# KMO_IO_MV5.net
KiCad netlist of a schematic drawn in EAGLE
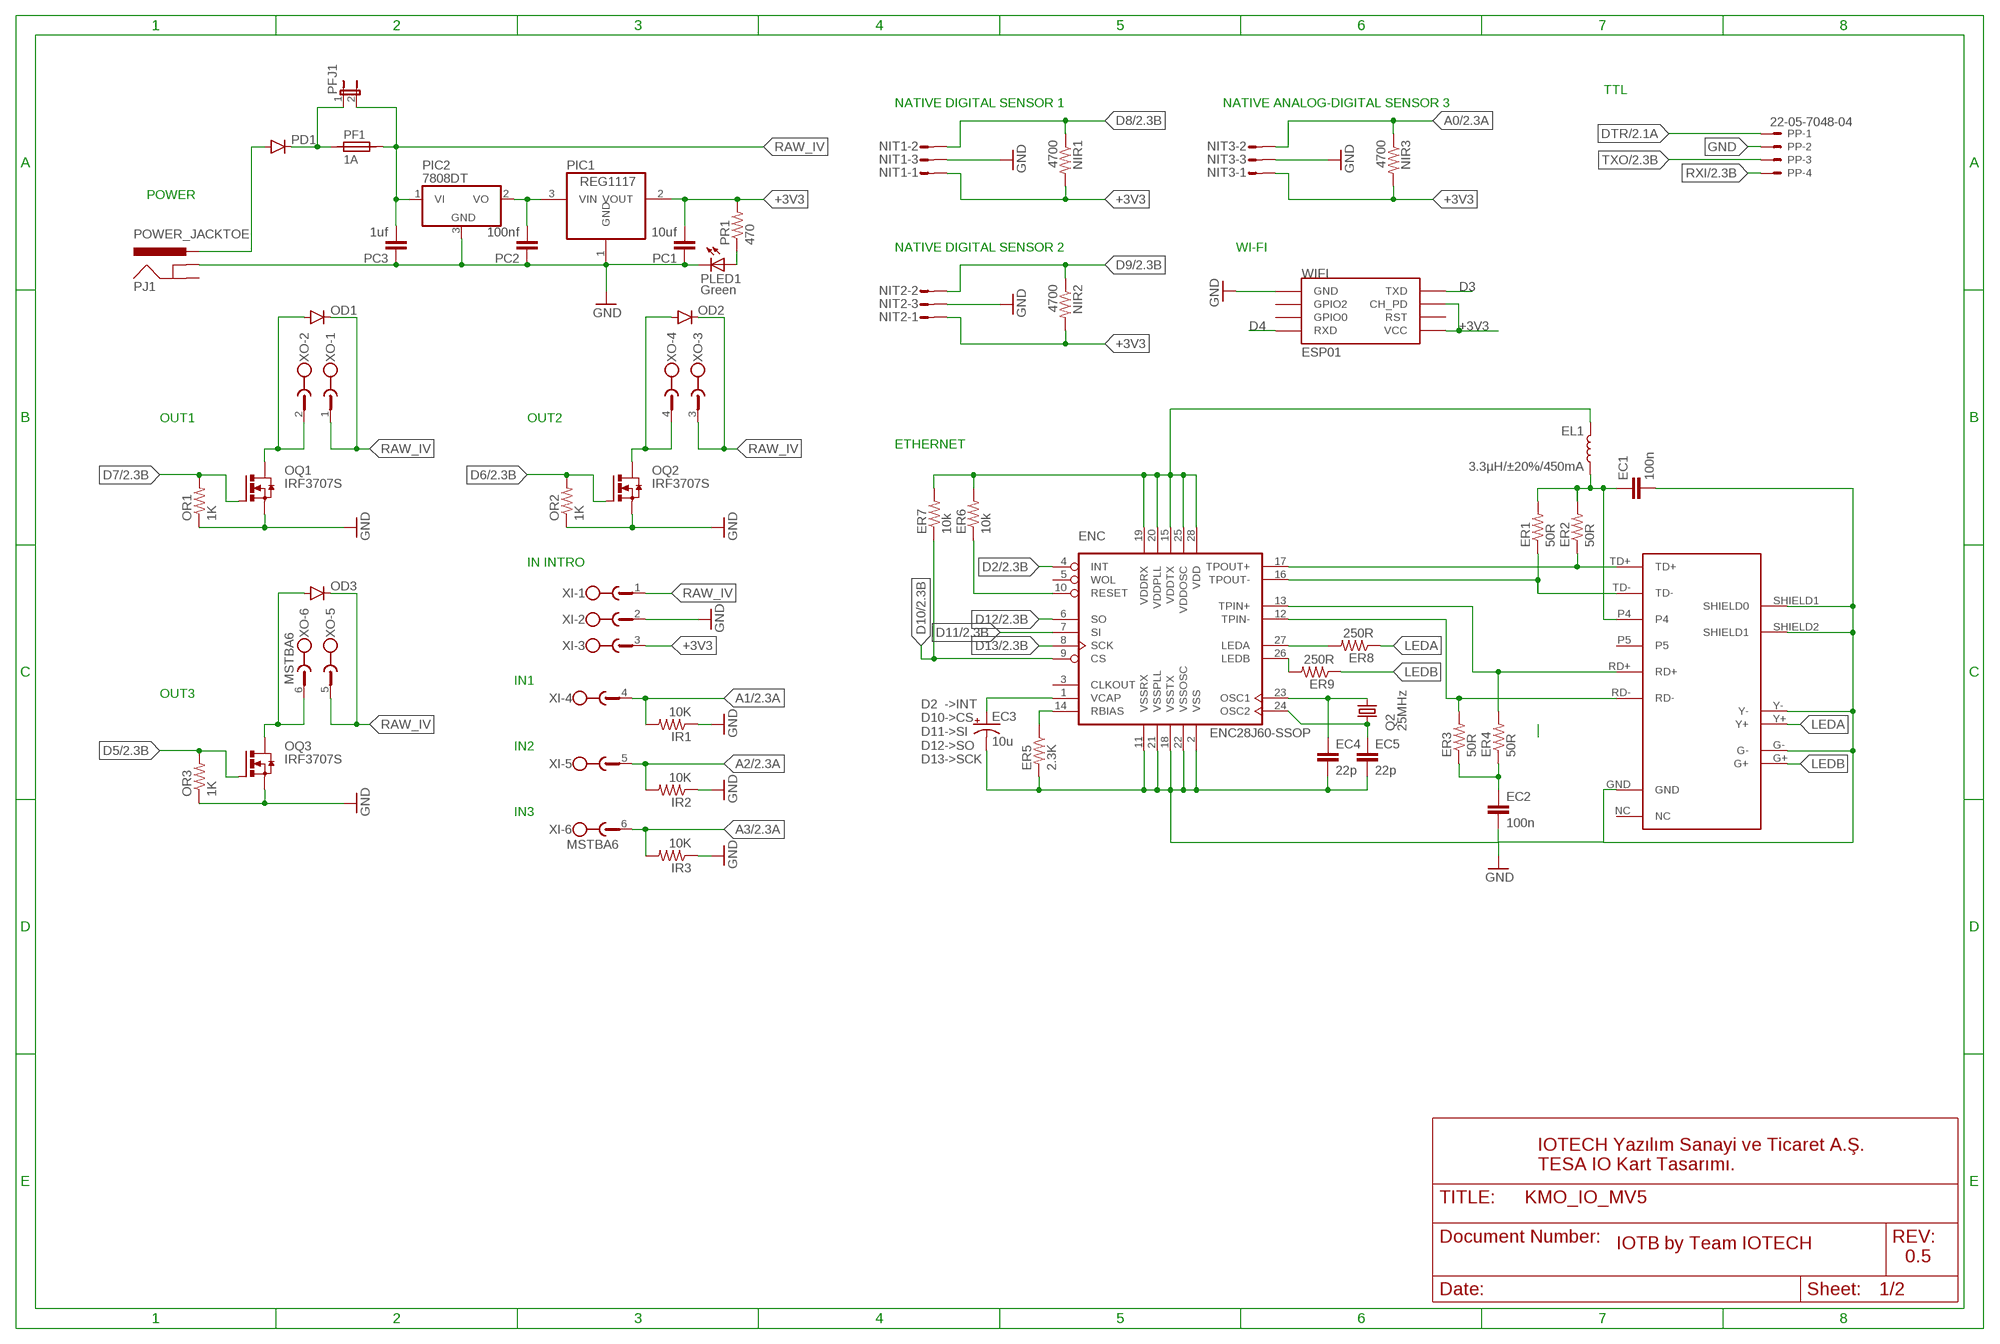
[diagram p0: schematic, sheet 1]
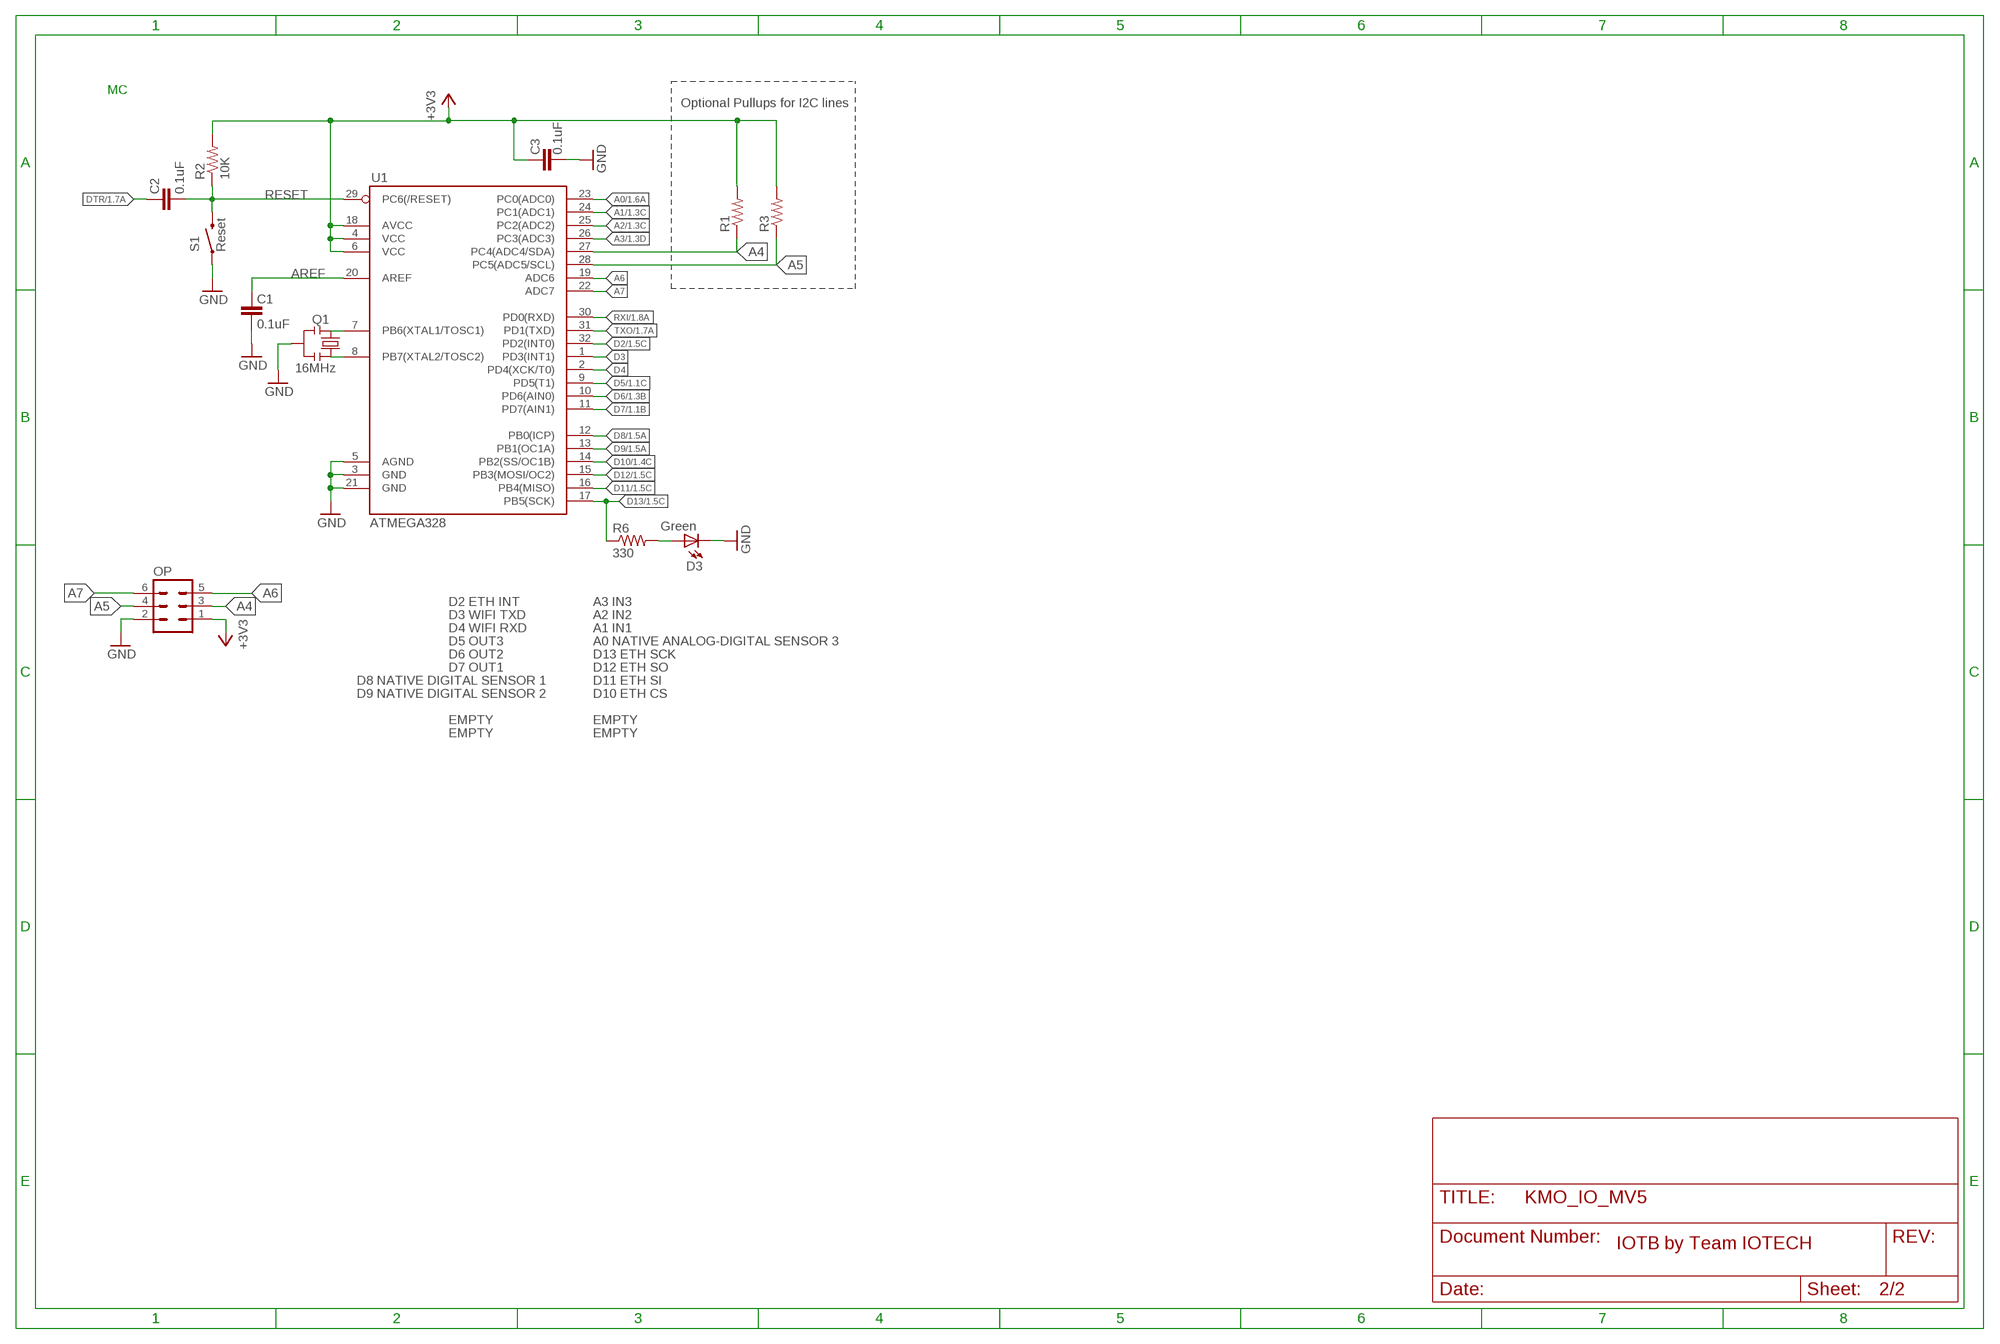
[diagram p1: schematic, sheet 2]

(export (version "E")
  (design (tool "Eeschema 10.0.6"))
  (components
    (comp (ref "C1")
      (value "0.1uF")
      (footprint "eagle-import:0805")
      (libsource (lib "eagle-import") (part "SparkFun-Passives_CAP0805"))
    )
    (comp (ref "C2")
      (value "0.1uF")
      (footprint "eagle-import:0805")
      (libsource (lib "eagle-import") (part "SparkFun-Passives_CAP0805"))
    )
    (comp (ref "C3")
      (value "0.1uF")
      (footprint "eagle-import:0805")
      (libsource (lib "eagle-import") (part "SparkFun-Passives_CAP0805"))
    )
    (comp (ref "D3")
      (value "Green")
      (footprint "eagle-import:CHIP-LED0805")
      (libsource (lib "eagle-import") (part "LEDCHIP-LED0805"))
    )
    (comp (ref "OP")
      (value "MA03-2")
      (footprint "eagle-import:MA03-2")
      (libsource (lib "eagle-import") (part "MA03-2"))
    )
    (comp (ref "Q1")
      (value "16MHz")
      (footprint "eagle-import:RESONATOR-SMD-1_1")
      (libsource (lib "eagle-import") (part "RESONATOR1{colon}1"))
    )
    (comp (ref "R1")
      (value "RESISTOR0805-RES")
      (footprint "eagle-import:0805")
      (libsource (lib "eagle-import") (part "RESISTOR0805-RES"))
    )
    (comp (ref "R2")
      (value "10K")
      (footprint "eagle-import:0805")
      (libsource (lib "eagle-import") (part "RESISTOR0805-RES"))
    )
    (comp (ref "R3")
      (value "RESISTOR0805-RES")
      (footprint "eagle-import:0805")
      (libsource (lib "eagle-import") (part "RESISTOR0805-RES"))
    )
    (comp (ref "R6")
      (value "330")
      (footprint "eagle-import:0805")
      (libsource (lib "eagle-import") (part "RESISTOR0805-RES"))
    )
    (comp (ref "S1")
      (value "Reset")
      (footprint "eagle-import:TACTILE-SWITCH-SMD-ALT01")
      (libsource (lib "eagle-import") (part "SWITCH-MOMENTARY-2SMD-ALT01"))
    )
    (comp (ref "U1")
      (value "ATMEGA328")
      (footprint "eagle-import:TQFP32-08")
      (libsource (lib "eagle-import") (part "ATMEGA168"))
    )
    (comp (ref "EC1")
      (value "100n")
      (footprint "eagle-import:0805")
      (libsource (lib "eagle-import") (part "SparkFun-Passives_CAP0805"))
    )
    (comp (ref "EC2")
      (value "100n")
      (footprint "eagle-import:0805")
      (libsource (lib "eagle-import") (part "SparkFun-Passives_CAP0805"))
    )
    (comp (ref "EC3")
      (value "10u")
      (footprint "eagle-import:EIA3216-KIT")
      (libsource (lib "eagle-import") (part "CAP_POL1206-KIT"))
    )
    (comp (ref "EC4")
      (value "22p")
      (footprint "eagle-import:0805")
      (libsource (lib "eagle-import") (part "SparkFun-Passives_CAP0805"))
    )
    (comp (ref "EC5")
      (value "22p")
      (footprint "eagle-import:0805")
      (libsource (lib "eagle-import") (part "SparkFun-Passives_CAP0805"))
    )
    (comp (ref "EL1")
      (value "3.3µH/±20%/450mA")
      (footprint "eagle-import:0805")
      (libsource (lib "eagle-import") (part "INDUCTOR-0805-3.3UH"))
    )
    (comp (ref "ENC")
      (value "ENC28J60-SSOP")
      (footprint "eagle-import:SSOP28")
      (libsource (lib "eagle-import") (part "ENC28J60-SSOP"))
    )
    (comp (ref "ER1")
      (value "50R")
      (footprint "eagle-import:0805")
      (libsource (lib "eagle-import") (part "RESISTOR0805-RES"))
    )
    (comp (ref "ER2")
      (value "50R")
      (footprint "eagle-import:0805")
      (libsource (lib "eagle-import") (part "RESISTOR0805-RES"))
    )
    (comp (ref "ER3")
      (value "50R")
      (footprint "eagle-import:0805")
      (libsource (lib "eagle-import") (part "RESISTOR0805-RES"))
    )
    (comp (ref "ER4")
      (value "50R")
      (footprint "eagle-import:0805")
      (libsource (lib "eagle-import") (part "RESISTOR0805-RES"))
    )
    (comp (ref "ER5")
      (value "2.3K")
      (footprint "eagle-import:0805")
      (libsource (lib "eagle-import") (part "RESISTOR0805-RES"))
    )
    (comp (ref "ER6")
      (value "10k")
      (footprint "eagle-import:0805")
      (libsource (lib "eagle-import") (part "RESISTOR0805-RES"))
    )
    (comp (ref "ER7")
      (value "10k")
      (footprint "eagle-import:0805")
      (libsource (lib "eagle-import") (part "RESISTOR0805-RES"))
    )
    (comp (ref "ER8")
      (value "250R")
      (footprint "eagle-import:0805")
      (libsource (lib "eagle-import") (part "RESISTOR0805-RES"))
    )
    (comp (ref "ER9")
      (value "250R")
      (footprint "eagle-import:0805")
      (libsource (lib "eagle-import") (part "RESISTOR0805-RES"))
    )
    (comp (ref "IR1")
      (value "10K")
      (footprint "eagle-import:0805")
      (libsource (lib "eagle-import") (part "RESISTOR0805-RES"))
    )
    (comp (ref "IR2")
      (value "10K")
      (footprint "eagle-import:0805")
      (libsource (lib "eagle-import") (part "RESISTOR0805-RES"))
    )
    (comp (ref "IR3")
      (value "10K")
      (footprint "eagle-import:0805")
      (libsource (lib "eagle-import") (part "RESISTOR0805-RES"))
    )
    (comp (ref "NIR1")
      (value "4700")
      (footprint "eagle-import:0805")
      (libsource (lib "eagle-import") (part "RESISTOR0805-RES"))
    )
    (comp (ref "NIR2")
      (value "4700")
      (footprint "eagle-import:0805")
      (libsource (lib "eagle-import") (part "RESISTOR0805-RES"))
    )
    (comp (ref "NIR3")
      (value "4700")
      (footprint "eagle-import:0805")
      (libsource (lib "eagle-import") (part "RESISTOR0805-RES"))
    )
    (comp (ref "NIT1")
      (value "S03P")
      (footprint "eagle-import:S03P")
      (libsource (lib "eagle-import") (part "S03P"))
    )
    (comp (ref "NIT2")
      (value "S03P")
      (footprint "eagle-import:S03P")
      (libsource (lib "eagle-import") (part "S03P"))
    )
    (comp (ref "NIT3")
      (value "S03P")
      (footprint "eagle-import:S03P")
      (libsource (lib "eagle-import") (part "S03P"))
    )
    (comp (ref "OD1")
      (value "DIODESMA")
      (footprint "eagle-import:SMA-DIODE")
      (libsource (lib "eagle-import") (part "DIODESMA"))
    )
    (comp (ref "OD2")
      (value "DIODESMA")
      (footprint "eagle-import:SMA-DIODE")
      (libsource (lib "eagle-import") (part "DIODESMA"))
    )
    (comp (ref "OD3")
      (value "DIODESMA")
      (footprint "eagle-import:SMA-DIODE")
      (libsource (lib "eagle-import") (part "DIODESMA"))
    )
    (comp (ref "OQ1")
      (value "IRF3707S")
      (footprint "eagle-import:D2PACK")
      (libsource (lib "eagle-import") (part "IRF3704S"))
    )
    (comp (ref "OQ2")
      (value "IRF3707S")
      (footprint "eagle-import:D2PACK")
      (libsource (lib "eagle-import") (part "IRF3704S"))
    )
    (comp (ref "OQ3")
      (value "IRF3707S")
      (footprint "eagle-import:D2PACK")
      (libsource (lib "eagle-import") (part "IRF3704S"))
    )
    (comp (ref "OR1")
      (value "1K")
      (footprint "eagle-import:0805")
      (libsource (lib "eagle-import") (part "RESISTOR0805-RES"))
    )
    (comp (ref "OR2")
      (value "1K")
      (footprint "eagle-import:0805")
      (libsource (lib "eagle-import") (part "RESISTOR0805-RES"))
    )
    (comp (ref "OR3")
      (value "1K")
      (footprint "eagle-import:0805")
      (libsource (lib "eagle-import") (part "RESISTOR0805-RES"))
    )
    (comp (ref "PC1")
      (value "10uf")
      (footprint "eagle-import:0805")
      (libsource (lib "eagle-import") (part "CAP0805"))
    )
    (comp (ref "PC2")
      (value "100nf")
      (footprint "eagle-import:0805")
      (libsource (lib "eagle-import") (part "CAP0805"))
    )
    (comp (ref "PC3")
      (value "1uf")
      (footprint "eagle-import:0805")
      (libsource (lib "eagle-import") (part "CAP0805"))
    )
    (comp (ref "PD1")
      (value "DIODESMA")
      (footprint "eagle-import:SMA-DIODE")
      (libsource (lib "eagle-import") (part "DIODESMA"))
    )
    (comp (ref "PF1")
      (value "1A")
      (footprint "eagle-import:1820")
      (libsource (lib "eagle-import") (part "SIBA194600"))
    )
    (comp (ref "PFJ1")
      (value "JP1E")
      (footprint "eagle-import:JP1")
      (libsource (lib "eagle-import") (part "JP1E"))
    )
    (comp (ref "PIC1")
      (value "REG1117")
      (footprint "eagle-import:SOT223")
      (libsource (lib "eagle-import") (part "REG1117"))
    )
    (comp (ref "PIC2")
      (value "7808DT")
      (footprint "eagle-import:TO252")
      (libsource (lib "eagle-import") (part "78DT08"))
    )
    (comp (ref "PJ1")
      (value "POWER_JACKTOE")
      (footprint "eagle-import:POWER_JACK_SMD_OVERPASTE_TOE")
      (libsource (lib "eagle-import") (part "POWER_JACKTOE"))
    )
    (comp (ref "PLED1")
      (value "Green")
      (footprint "eagle-import:CHIP-LED0805")
      (libsource (lib "eagle-import") (part "LEDCHIP-LED0805"))
    )
    (comp (ref "PP")
      (value "22-05-7048-04")
      (footprint "eagle-import:7395-04")
      (fields (field (name "MF") "MOLEX"))
      (libsource (lib "eagle-import") (part "22-?-0405-7048"))
    )
    (comp (ref "PR1")
      (value "470")
      (footprint "eagle-import:0805")
      (libsource (lib "eagle-import") (part "RESISTOR0805-RES"))
    )
    (comp (ref "Q2")
      (value "25MHz")
      (footprint "eagle-import:5.0X3.2_2")
      (libsource (lib "eagle-import") (part "KX-9B"))
    )
    (comp (ref "U$2")
      (value "HR911105A")
      (footprint "eagle-import:RJ45")
      (libsource (lib "eagle-import") (part "HR911105A"))
    )
    (comp (ref "WIFI")
      (value "ESP01")
      (footprint "eagle-import:ESP01")
      (libsource (lib "eagle-import") (part "ESP01"))
    )
    (comp (ref "XI")
      (value "MSTBA6")
      (footprint "eagle-import:MSTBA6")
      (fields (field (name "MF") "FARNELL") (field (name "MPN") "1757284"))
      (libsource (lib "eagle-import") (part "MSTBA6"))
    )
    (comp (ref "XO")
      (value "MSTBA6")
      (footprint "eagle-import:MSTBA6")
      (fields (field (name "MF") "FARNELL") (field (name "MPN") "1757284"))
      (libsource (lib "eagle-import") (part "MSTBA6"))
    )
  )
  (nets
    (net (code "1") (name "+3V3") (class "Default")
      (node (ref "C3") (pin "2") (pinfunction "2_2") (pintype "passive"))
      (node (ref "EL1") (pin "1") (pinfunction "1_1") (pintype "passive"))
      (node (ref "ENC") (pin "15") (pinfunction "VDDTX_15") (pintype "power_in"))
      (node (ref "ENC") (pin "19") (pinfunction "VDDRX_19") (pintype "power_in"))
      (node (ref "ENC") (pin "20") (pinfunction "VDDPLL_20") (pintype "power_in"))
      (node (ref "ENC") (pin "25") (pinfunction "VDDOSC_25") (pintype "power_in"))
      (node (ref "ENC") (pin "28") (pinfunction "VDD_28") (pintype "power_in"))
      (node (ref "ER6") (pin "2") (pinfunction "2_2") (pintype "passive"))
      (node (ref "ER7") (pin "2") (pinfunction "2_2") (pintype "passive"))
      (node (ref "NIR1") (pin "2") (pinfunction "2_2") (pintype "passive"))
      (node (ref "NIR2") (pin "2") (pinfunction "2_2") (pintype "passive"))
      (node (ref "NIR3") (pin "2") (pinfunction "2_2") (pintype "passive"))
      (node (ref "NIT1") (pin "1") (pinfunction "S_1") (pintype "passive"))
      (node (ref "NIT2") (pin "1") (pinfunction "S_1") (pintype "passive"))
      (node (ref "NIT3") (pin "1") (pinfunction "S_1") (pintype "passive"))
      (node (ref "OP") (pin "1") (pinfunction "1_1") (pintype "passive"))
      (node (ref "PC1") (pin "2") (pinfunction "2_2") (pintype "passive"))
      (node (ref "PIC1") (pin "2") (pinfunction "VOUT_2") (pintype "output"))
      (node (ref "PR1") (pin "2") (pinfunction "2_2") (pintype "passive"))
      (node (ref "R1") (pin "2") (pinfunction "2_2") (pintype "passive"))
      (node (ref "R2") (pin "2") (pinfunction "2_2") (pintype "passive"))
      (node (ref "R3") (pin "2") (pinfunction "2_2") (pintype "passive"))
      (node (ref "U1") (pin "18") (pinfunction "AVCC_18") (pintype "bidirectional"))
      (node (ref "U1") (pin "4") (pinfunction "VCC_4") (pintype "bidirectional"))
      (node (ref "U1") (pin "6") (pinfunction "VCC_6") (pintype "bidirectional"))
      (node (ref "WIFI") (pin "CH_PD") (pinfunction "CH_PD_CH_PD") (pintype "bidirectional"))
      (node (ref "WIFI") (pin "VCC") (pinfunction "VCC_VCC") (pintype "bidirectional"))
      (node (ref "XI") (pin "3") (pinfunction "1_3") (pintype "passive"))
    )
    (net (code "2") (name "A0") (class "Default")
      (node (ref "NIR3") (pin "1") (pinfunction "1_1") (pintype "passive"))
      (node (ref "NIT3") (pin "2") (pinfunction "S_2") (pintype "passive"))
      (node (ref "U1") (pin "23") (pinfunction "PC0(ADC0)_23") (pintype "bidirectional"))
    )
    (net (code "3") (name "A1") (class "Default")
      (node (ref "IR1") (pin "2") (pinfunction "2_2") (pintype "passive"))
      (node (ref "U1") (pin "24") (pinfunction "PC1(ADC1)_24") (pintype "bidirectional"))
      (node (ref "XI") (pin "4") (pinfunction "1_4") (pintype "passive"))
    )
    (net (code "4") (name "A2") (class "Default")
      (node (ref "IR2") (pin "2") (pinfunction "2_2") (pintype "passive"))
      (node (ref "U1") (pin "25") (pinfunction "PC2(ADC2)_25") (pintype "bidirectional"))
      (node (ref "XI") (pin "5") (pinfunction "1_5") (pintype "passive"))
    )
    (net (code "5") (name "A3") (class "Default")
      (node (ref "IR3") (pin "2") (pinfunction "2_2") (pintype "passive"))
      (node (ref "U1") (pin "26") (pinfunction "PC3(ADC3)_26") (pintype "bidirectional"))
      (node (ref "XI") (pin "6") (pinfunction "1_6") (pintype "passive"))
    )
    (net (code "6") (name "A4") (class "Default")
      (node (ref "OP") (pin "3") (pinfunction "3_3") (pintype "passive"))
      (node (ref "R1") (pin "1") (pinfunction "1_1") (pintype "passive"))
      (node (ref "U1") (pin "27") (pinfunction "PC4(ADC4/SDA)_27") (pintype "bidirectional"))
    )
    (net (code "7") (name "A5") (class "Default")
      (node (ref "OP") (pin "4") (pinfunction "4_4") (pintype "passive"))
      (node (ref "R3") (pin "1") (pinfunction "1_1") (pintype "passive"))
      (node (ref "U1") (pin "28") (pinfunction "PC5(ADC5/SCL)_28") (pintype "bidirectional"))
    )
    (net (code "8") (name "A6") (class "Default")
      (node (ref "OP") (pin "5") (pinfunction "5_5") (pintype "passive"))
      (node (ref "U1") (pin "19") (pinfunction "ADC6_19") (pintype "bidirectional"))
    )
    (net (code "9") (name "A7") (class "Default")
      (node (ref "OP") (pin "6") (pinfunction "6_6") (pintype "passive"))
      (node (ref "U1") (pin "22") (pinfunction "ADC7_22") (pintype "bidirectional"))
    )
    (net (code "10") (name "AREF") (class "Default")
      (node (ref "C1") (pin "2") (pinfunction "2_2") (pintype "passive"))
      (node (ref "U1") (pin "20") (pinfunction "AREF_20") (pintype "bidirectional"))
    )
    (net (code "11") (name "D2") (class "Default")
      (node (ref "ENC") (pin "4") (pinfunction "INT_4") (pintype "output"))
      (node (ref "U1") (pin "32") (pinfunction "PD2(INT0)_32") (pintype "bidirectional"))
    )
    (net (code "12") (name "D3") (class "Default")
      (node (ref "U1") (pin "1") (pinfunction "PD3(INT1)_1") (pintype "bidirectional"))
      (node (ref "WIFI") (pin "TX") (pinfunction "TXD_TX") (pintype "bidirectional"))
    )
    (net (code "13") (name "D4") (class "Default")
      (node (ref "U1") (pin "2") (pinfunction "PD4(XCK/T0)_2") (pintype "bidirectional"))
      (node (ref "WIFI") (pin "RX") (pinfunction "RXD_RX") (pintype "bidirectional"))
    )
    (net (code "14") (name "D5") (class "Default")
      (node (ref "OQ3") (pin "1") (pinfunction "G_1") (pintype "passive"))
      (node (ref "OR3") (pin "2") (pinfunction "2_2") (pintype "passive"))
      (node (ref "U1") (pin "9") (pinfunction "PD5(T1)_9") (pintype "bidirectional"))
    )
    (net (code "15") (name "D6") (class "Default")
      (node (ref "OQ2") (pin "1") (pinfunction "G_1") (pintype "passive"))
      (node (ref "OR2") (pin "2") (pinfunction "2_2") (pintype "passive"))
      (node (ref "U1") (pin "10") (pinfunction "PD6(AIN0)_10") (pintype "bidirectional"))
    )
    (net (code "16") (name "D7") (class "Default")
      (node (ref "OQ1") (pin "1") (pinfunction "G_1") (pintype "passive"))
      (node (ref "OR1") (pin "2") (pinfunction "2_2") (pintype "passive"))
      (node (ref "U1") (pin "11") (pinfunction "PD7(AIN1)_11") (pintype "bidirectional"))
    )
    (net (code "17") (name "D8") (class "Default")
      (node (ref "NIR1") (pin "1") (pinfunction "1_1") (pintype "passive"))
      (node (ref "NIT1") (pin "2") (pinfunction "S_2") (pintype "passive"))
      (node (ref "U1") (pin "12") (pinfunction "PB0(ICP)_12") (pintype "bidirectional"))
    )
    (net (code "18") (name "D9") (class "Default")
      (node (ref "NIR2") (pin "1") (pinfunction "1_1") (pintype "passive"))
      (node (ref "NIT2") (pin "2") (pinfunction "S_2") (pintype "passive"))
      (node (ref "U1") (pin "13") (pinfunction "PB1(OC1A)_13") (pintype "bidirectional"))
    )
    (net (code "19") (name "D10") (class "Default")
      (node (ref "ENC") (pin "9") (pinfunction "CS_9") (pintype "input"))
      (node (ref "ER7") (pin "1") (pinfunction "1_1") (pintype "passive"))
      (node (ref "U1") (pin "14") (pinfunction "PB2(SS/OC1B)_14") (pintype "bidirectional"))
    )
    (net (code "20") (name "D11") (class "Default")
      (node (ref "ENC") (pin "7") (pinfunction "SI_7") (pintype "input"))
      (node (ref "U1") (pin "16") (pinfunction "PB4(MISO)_16") (pintype "bidirectional"))
    )
    (net (code "21") (name "D12") (class "Default")
      (node (ref "ENC") (pin "6") (pinfunction "SO_6") (pintype "output"))
      (node (ref "U1") (pin "15") (pinfunction "PB3(MOSI/OC2)_15") (pintype "bidirectional"))
    )
    (net (code "22") (name "D13") (class "Default")
      (node (ref "ENC") (pin "8") (pinfunction "SCK_8") (pintype "input"))
      (node (ref "R6") (pin "1") (pinfunction "1_1") (pintype "passive"))
      (node (ref "U1") (pin "17") (pinfunction "PB5(SCK)_17") (pintype "bidirectional"))
    )
    (net (code "23") (name "DTR") (class "Default")
      (node (ref "C2") (pin "2") (pinfunction "2_2") (pintype "passive"))
      (node (ref "PP") (pin "1") (pinfunction "S_1") (pintype "passive"))
    )
    (net (code "24") (name "GND") (class "Default")
      (node (ref "C1") (pin "1") (pinfunction "1_1") (pintype "passive"))
      (node (ref "C3") (pin "1") (pinfunction "1_1") (pintype "passive"))
      (node (ref "D3") (pin "C") (pinfunction "C_C") (pintype "passive"))
      (node (ref "EC1") (pin "2") (pinfunction "2_2") (pintype "passive"))
      (node (ref "EC2") (pin "2") (pinfunction "2_2") (pintype "passive"))
      (node (ref "EC3") (pin "C") (pinfunction "-_C") (pintype "passive"))
      (node (ref "EC4") (pin "2") (pinfunction "2_2") (pintype "passive"))
      (node (ref "EC5") (pin "2") (pinfunction "2_2") (pintype "passive"))
      (node (ref "ENC") (pin "11") (pinfunction "VSSRX_11") (pintype "power_in"))
      (node (ref "ENC") (pin "18") (pinfunction "VSSTX_18") (pintype "power_in"))
      (node (ref "ENC") (pin "2") (pinfunction "VSS_2") (pintype "power_in"))
      (node (ref "ENC") (pin "21") (pinfunction "VSSPLL_21") (pintype "power_in"))
      (node (ref "ENC") (pin "22") (pinfunction "VSSOSC_22") (pintype "power_in"))
      (node (ref "ER5") (pin "2") (pinfunction "2_2") (pintype "passive"))
      (node (ref "IR1") (pin "1") (pinfunction "1_1") (pintype "passive"))
      (node (ref "IR2") (pin "1") (pinfunction "1_1") (pintype "passive"))
      (node (ref "IR3") (pin "1") (pinfunction "1_1") (pintype "passive"))
      (node (ref "NIT1") (pin "3") (pinfunction "S_3") (pintype "passive"))
      (node (ref "NIT2") (pin "3") (pinfunction "S_3") (pintype "passive"))
      (node (ref "NIT3") (pin "3") (pinfunction "S_3") (pintype "passive"))
      (node (ref "OP") (pin "2") (pinfunction "2_2") (pintype "passive"))
      (node (ref "OQ1") (pin "3") (pinfunction "S_3") (pintype "passive"))
      (node (ref "OQ2") (pin "3") (pinfunction "S_3") (pintype "passive"))
      (node (ref "OQ3") (pin "3") (pinfunction "S_3") (pintype "passive"))
      (node (ref "OR1") (pin "1") (pinfunction "1_1") (pintype "passive"))
      (node (ref "OR2") (pin "1") (pinfunction "1_1") (pintype "passive"))
      (node (ref "OR3") (pin "1") (pinfunction "1_1") (pintype "passive"))
      (node (ref "PC1") (pin "1") (pinfunction "1_1") (pintype "passive"))
      (node (ref "PC2") (pin "1") (pinfunction "1_1") (pintype "passive"))
      (node (ref "PC3") (pin "1") (pinfunction "1_1") (pintype "passive"))
      (node (ref "PIC1") (pin "1") (pinfunction "GND_1") (pintype "power_in"))
      (node (ref "PIC2") (pin "3") (pinfunction "GND_3") (pintype "passive"))
      (node (ref "PJ1") (pin "GND") (pinfunction "GNDBREAK_GND") (pintype "bidirectional"))
      (node (ref "PLED1") (pin "C") (pinfunction "C_C") (pintype "passive"))
      (node (ref "PP") (pin "2") (pinfunction "S_2") (pintype "passive"))
      (node (ref "Q1") (pin "2") (pinfunction "2_2") (pintype "passive"))
      (node (ref "S1") (pin "1") (pinfunction "1_1") (pintype "passive"))
      (node (ref "S1") (pin "2") (pinfunction "1_2") (pintype "passive"))
      (node (ref "U$2") (pin "G-") (pinfunction "G-_G-") (pintype "bidirectional"))
      (node (ref "U$2") (pin "GND") (pinfunction "GND_GND") (pintype "bidirectional"))
      (node (ref "U$2") (pin "SHIELD1") (pinfunction "SHIELD0_SHIELD1") (pintype "bidirectional"))
      (node (ref "U$2") (pin "SHIELD2") (pinfunction "SHIELD1_SHIELD2") (pintype "bidirectional"))
      (node (ref "U$2") (pin "Y-") (pinfunction "Y-_Y-") (pintype "bidirectional"))
      (node (ref "U1") (pin "21") (pinfunction "GND_21") (pintype "bidirectional"))
      (node (ref "U1") (pin "3") (pinfunction "GND_3") (pintype "bidirectional"))
      (node (ref "U1") (pin "5") (pinfunction "AGND_5") (pintype "bidirectional"))
      (node (ref "WIFI") (pin "GND") (pinfunction "GND_GND") (pintype "bidirectional"))
      (node (ref "XI") (pin "2") (pinfunction "1_2") (pintype "passive"))
    )
    (net (code "25") (name "LEDA") (class "Default")
      (node (ref "ER8") (pin "1") (pinfunction "1_1") (pintype "passive"))
      (node (ref "U$2") (pin "Y+") (pinfunction "Y+_Y+") (pintype "bidirectional"))
    )
    (net (code "26") (name "LEDB") (class "Default")
      (node (ref "ER9") (pin "1") (pinfunction "1_1") (pintype "passive"))
      (node (ref "U$2") (pin "G+") (pinfunction "G+_G+") (pintype "bidirectional"))
    )
    (net (code "27") (name "Net-(D3-PadA)") (class "Default")
      (node (ref "D3") (pin "A") (pinfunction "A_A") (pintype "passive"))
      (node (ref "R6") (pin "2") (pinfunction "2_2") (pintype "passive"))
    )
    (net (code "28") (name "Net-(EC1-Pad1)") (class "Default")
      (node (ref "EC1") (pin "1") (pinfunction "1_1") (pintype "passive"))
      (node (ref "EL1") (pin "2") (pinfunction "2_2") (pintype "passive"))
      (node (ref "ER1") (pin "2") (pinfunction "2_2") (pintype "passive"))
      (node (ref "ER2") (pin "2") (pinfunction "2_2") (pintype "passive"))
      (node (ref "U$2") (pin "P4") (pinfunction "P4_P4") (pintype "bidirectional"))
    )
    (net (code "29") (name "Net-(EC2-Pad1)") (class "Default")
      (node (ref "EC2") (pin "1") (pinfunction "1_1") (pintype "passive"))
      (node (ref "ER3") (pin "1") (pinfunction "1_1") (pintype "passive"))
      (node (ref "ER4") (pin "1") (pinfunction "1_1") (pintype "passive"))
    )
    (net (code "30") (name "Net-(EC3-+)") (class "Default")
      (node (ref "EC3") (pin "A") (pinfunction "+_A") (pintype "passive"))
      (node (ref "ENC") (pin "1") (pinfunction "VCAP_1") (pintype "power_in"))
    )
    (net (code "31") (name "Net-(ENC-LEDA)") (class "Default")
      (node (ref "ENC") (pin "27") (pinfunction "LEDA_27") (pintype "output"))
      (node (ref "ER8") (pin "2") (pinfunction "2_2") (pintype "passive"))
    )
    (net (code "32") (name "Net-(ENC-LEDB)") (class "Default")
      (node (ref "ENC") (pin "26") (pinfunction "LEDB_26") (pintype "output"))
      (node (ref "ER9") (pin "2") (pinfunction "2_2") (pintype "passive"))
    )
    (net (code "33") (name "Net-(ENC-OSC1)") (class "Default")
      (node (ref "EC4") (pin "1") (pinfunction "1_1") (pintype "passive"))
      (node (ref "ENC") (pin "23") (pinfunction "OSC1_23") (pintype "input"))
      (node (ref "Q2") (pin "2") (pinfunction "2_2") (pintype "passive"))
    )
    (net (code "34") (name "Net-(ENC-OSC2)") (class "Default")
      (node (ref "EC5") (pin "1") (pinfunction "1_1") (pintype "passive"))
      (node (ref "ENC") (pin "24") (pinfunction "OSC2_24") (pintype "output"))
      (node (ref "Q2") (pin "1") (pinfunction "1_1") (pintype "passive"))
    )
    (net (code "35") (name "Net-(ENC-RBIAS)") (class "Default")
      (node (ref "ENC") (pin "14") (pinfunction "RBIAS_14") (pintype "passive"))
      (node (ref "ER5") (pin "1") (pinfunction "1_1") (pintype "passive"))
    )
    (net (code "36") (name "Net-(ENC-RESET)") (class "Default")
      (node (ref "ENC") (pin "10") (pinfunction "RESET_10") (pintype "input"))
      (node (ref "ER6") (pin "1") (pinfunction "1_1") (pintype "passive"))
    )
    (net (code "37") (name "Net-(ENC-TPIN+)") (class "Default")
      (node (ref "ENC") (pin "13") (pinfunction "TPIN+_13") (pintype "input"))
      (node (ref "ER4") (pin "2") (pinfunction "2_2") (pintype "passive"))
      (node (ref "U$2") (pin "RD+") (pinfunction "RD+_RD+") (pintype "bidirectional"))
    )
    (net (code "38") (name "Net-(ENC-TPIN-)") (class "Default")
      (node (ref "ENC") (pin "12") (pinfunction "TPIN-_12") (pintype "input"))
      (node (ref "ER3") (pin "2") (pinfunction "2_2") (pintype "passive"))
      (node (ref "U$2") (pin "RD-") (pinfunction "RD-_RD-") (pintype "bidirectional"))
    )
    (net (code "39") (name "Net-(ENC-TPOUT+)") (class "Default")
      (node (ref "ENC") (pin "17") (pinfunction "TPOUT+_17") (pintype "output"))
      (node (ref "ER2") (pin "1") (pinfunction "1_1") (pintype "passive"))
      (node (ref "U$2") (pin "TD+") (pinfunction "TD+_TD+") (pintype "bidirectional"))
    )
    (net (code "40") (name "Net-(ENC-TPOUT-)") (class "Default")
      (node (ref "ENC") (pin "16") (pinfunction "TPOUT-_16") (pintype "output"))
      (node (ref "ER1") (pin "1") (pinfunction "1_1") (pintype "passive"))
      (node (ref "U$2") (pin "TD-") (pinfunction "TD-_TD-") (pintype "bidirectional"))
    )
    (net (code "41") (name "Net-(OQ1-D)") (class "Default")
      (node (ref "OD1") (pin "A") (pinfunction "A_A") (pintype "passive"))
      (node (ref "OQ1") (pin "2") (pinfunction "D_2") (pintype "passive"))
      (node (ref "XO") (pin "2") (pinfunction "1_2") (pintype "passive"))
    )
    (net (code "42") (name "Net-(OQ2-D)") (class "Default")
      (node (ref "OD2") (pin "A") (pinfunction "A_A") (pintype "passive"))
      (node (ref "OQ2") (pin "2") (pinfunction "D_2") (pintype "passive"))
      (node (ref "XO") (pin "4") (pinfunction "1_4") (pintype "passive"))
    )
    (net (code "43") (name "Net-(OQ3-D)") (class "Default")
      (node (ref "OD3") (pin "A") (pinfunction "A_A") (pintype "passive"))
      (node (ref "OQ3") (pin "2") (pinfunction "D_2") (pintype "passive"))
      (node (ref "XO") (pin "6") (pinfunction "1_6") (pintype "passive"))
    )
    (net (code "44") (name "Net-(PD1-PadC)") (class "Default")
      (node (ref "PD1") (pin "C") (pinfunction "C_C") (pintype "passive"))
      (node (ref "PF1") (pin "1") (pinfunction "1_1") (pintype "passive"))
      (node (ref "PFJ1") (pin "1") (pinfunction "1_1") (pintype "passive"))
    )
    (net (code "45") (name "Net-(PIC1-VIN)") (class "Default")
      (node (ref "PC2") (pin "2") (pinfunction "2_2") (pintype "passive"))
      (node (ref "PIC1") (pin "3") (pinfunction "VIN_3") (pintype "input"))
      (node (ref "PIC2") (pin "2") (pinfunction "VO_2") (pintype "passive"))
    )
    (net (code "46") (name "Net-(PJ1-PWR)") (class "Default")
      (node (ref "PD1") (pin "A") (pinfunction "A_A") (pintype "passive"))
      (node (ref "PJ1") (pin "VIN0") (pinfunction "PWR_VIN0") (pintype "bidirectional"))
    )
    (net (code "47") (name "Net-(PLED1-PadA)") (class "Default")
      (node (ref "PLED1") (pin "A") (pinfunction "A_A") (pintype "passive"))
      (node (ref "PR1") (pin "1") (pinfunction "1_1") (pintype "passive"))
    )
    (net (code "48") (name "Net-(U1-PB6(XTAL1{slash}TOSC1))") (class "Default")
      (node (ref "Q1") (pin "1") (pinfunction "1_1") (pintype "passive"))
      (node (ref "U1") (pin "7") (pinfunction "PB6(XTAL1/TOSC1)_7") (pintype "bidirectional"))
    )
    (net (code "49") (name "Net-(U1-PB7(XTAL2{slash}TOSC2))") (class "Default")
      (node (ref "Q1") (pin "3") (pinfunction "3_3") (pintype "passive"))
      (node (ref "U1") (pin "8") (pinfunction "PB7(XTAL2/TOSC2)_8") (pintype "bidirectional"))
    )
    (net (code "50") (name "RAW_IV") (class "Default")
      (node (ref "OD1") (pin "C") (pinfunction "C_C") (pintype "passive"))
      (node (ref "OD2") (pin "C") (pinfunction "C_C") (pintype "passive"))
      (node (ref "OD3") (pin "C") (pinfunction "C_C") (pintype "passive"))
      (node (ref "PC3") (pin "2") (pinfunction "2_2") (pintype "passive"))
      (node (ref "PF1") (pin "2") (pinfunction "2_2") (pintype "passive"))
      (node (ref "PFJ1") (pin "2") (pinfunction "2_2") (pintype "passive"))
      (node (ref "PIC2") (pin "1") (pinfunction "VI_1") (pintype "input"))
      (node (ref "XI") (pin "1") (pinfunction "1_1") (pintype "passive"))
      (node (ref "XO") (pin "1") (pinfunction "1_1") (pintype "passive"))
      (node (ref "XO") (pin "3") (pinfunction "1_3") (pintype "passive"))
      (node (ref "XO") (pin "5") (pinfunction "1_5") (pintype "passive"))
    )
    (net (code "51") (name "RESET") (class "Default")
      (node (ref "C2") (pin "1") (pinfunction "1_1") (pintype "passive"))
      (node (ref "R2") (pin "1") (pinfunction "1_1") (pintype "passive"))
      (node (ref "S1") (pin "3") (pinfunction "2_3") (pintype "passive"))
      (node (ref "S1") (pin "4") (pinfunction "2_4") (pintype "passive"))
      (node (ref "U1") (pin "29") (pinfunction "PC6(/RESET)_29") (pintype "bidirectional"))
    )
    (net (code "52") (name "RXI") (class "Default")
      (node (ref "PP") (pin "4") (pinfunction "S_4") (pintype "passive"))
      (node (ref "U1") (pin "30") (pinfunction "PD0(RXD)_30") (pintype "bidirectional"))
    )
    (net (code "53") (name "TXO") (class "Default")
      (node (ref "PP") (pin "3") (pinfunction "S_3") (pintype "passive"))
      (node (ref "U1") (pin "31") (pinfunction "PD1(TXD)_31") (pintype "bidirectional"))
    )
    (net (code "54") (name "unconnected-(ENC-CLKOUT-Pad3)") (class "Default")
      (node (ref "ENC") (pin "3") (pinfunction "CLKOUT_3") (pintype "output"))
    )
    (net (code "55") (name "unconnected-(ENC-WOL-Pad5)") (class "Default")
      (node (ref "ENC") (pin "5") (pinfunction "WOL_5") (pintype "output"))
    )
    (net (code "56") (name "unconnected-(PJ1-GND-PadP$4)") (class "Default")
      (node (ref "PJ1") (pin "P$4") (pinfunction "GND_P$4") (pintype "bidirectional"))
    )
    (net (code "57") (name "unconnected-(U$2-PadNC)") (class "Default")
      (node (ref "U$2") (pin "NC") (pinfunction "NC_NC") (pintype "bidirectional"))
    )
    (net (code "58") (name "unconnected-(U$2-PadP5)") (class "Default")
      (node (ref "U$2") (pin "P5") (pinfunction "P5_P5") (pintype "bidirectional"))
    )
    (net (code "59") (name "unconnected-(WIFI-PadGPIO0)") (class "Default")
      (node (ref "WIFI") (pin "GPIO0") (pinfunction "GPIO0_GPIO0") (pintype "bidirectional"))
    )
    (net (code "60") (name "unconnected-(WIFI-PadGPIO2)") (class "Default")
      (node (ref "WIFI") (pin "GPIO2") (pinfunction "GPIO2_GPIO2") (pintype "bidirectional"))
    )
    (net (code "61") (name "unconnected-(WIFI-PadRST)") (class "Default")
      (node (ref "WIFI") (pin "RST") (pinfunction "RST_RST") (pintype "bidirectional"))
    )
  )
)
